# Control_part.net
KiCad netlist of a schematic drawn in Altium Designer
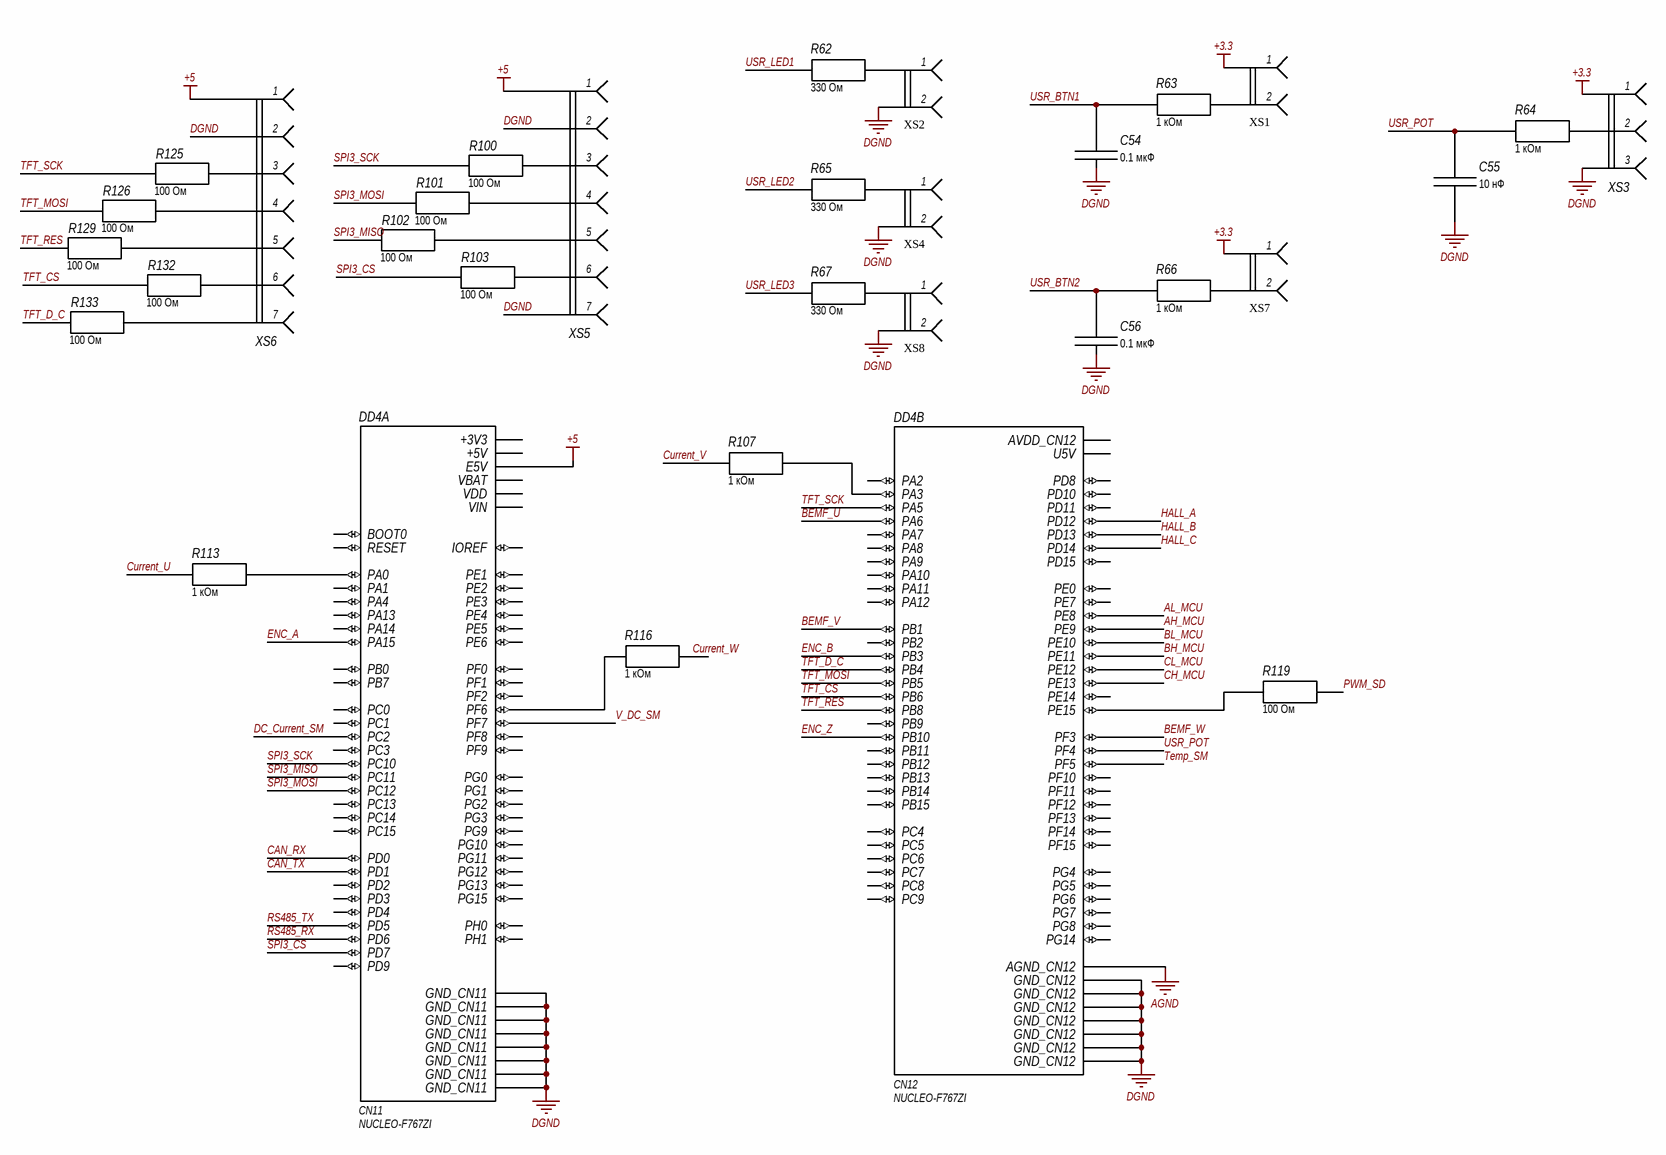
[diagram p0: Control_part.SchDoc]

(export (version "E")
  (design (tool "Eeschema 10.0.6"))
  (components
    (comp (ref "C54")
      (value "0.1 мкФ")
      (footprint "CC0603")
      (fields (field (name "VOLTAGE") "50 В") (field (name "Comment") "Capacitor"))
      (libsource (lib "Main_components") (part "Capacitor"))
    )
    (comp (ref "C55")
      (value "10 нФ")
      (footprint "CC0603")
      (fields (field (name "VOLTAGE") "50 В") (field (name "Comment") "Capacitor"))
      (libsource (lib "Main_components") (part "Capacitor"))
    )
    (comp (ref "C56")
      (value "0.1 мкФ")
      (footprint "CC0603")
      (fields (field (name "VOLTAGE") "50 В") (field (name "Comment") "Capacitor"))
      (libsource (lib "Main_components") (part "Capacitor"))
    )
    (comp (ref "DD4")
      (value "NUCLEO-F767ZI")
      (footprint "ST_NUCLEO-F767ZI")
      (fields (field (name "MF") "STMicroelectronics") (field (name "MP") "NUCLEO-F429ZI"))
      (libsource (lib "Microcircuits") (part "NUCLEO-F767ZI"))
    )
    (comp (ref "R62")
      (value "330 Ом")
      (footprint "RC1206")
      (fields (field (name "POWER") "250 мВт") (field (name "Comment") "Resistor"))
      (libsource (lib "Main_components") (part "Resistor"))
    )
    (comp (ref "R63")
      (value "1 кОм")
      (footprint "RC0603")
      (fields (field (name "POWER") "100 мВт") (field (name "Comment") "Resistor"))
      (libsource (lib "Main_components") (part "Resistor"))
    )
    (comp (ref "R64")
      (value "1 кОм")
      (footprint "RC0603")
      (fields (field (name "POWER") "100 мВт") (field (name "Comment") "Resistor"))
      (libsource (lib "Main_components") (part "Resistor"))
    )
    (comp (ref "R65")
      (value "330 Ом")
      (footprint "RC1206")
      (fields (field (name "POWER") "250 мВт") (field (name "Comment") "Resistor"))
      (libsource (lib "Main_components") (part "Resistor"))
    )
    (comp (ref "R66")
      (value "1 кОм")
      (footprint "RC0603")
      (fields (field (name "POWER") "100 мВт") (field (name "Comment") "Resistor"))
      (libsource (lib "Main_components") (part "Resistor"))
    )
    (comp (ref "R67")
      (value "330 Ом")
      (footprint "RC1206")
      (fields (field (name "POWER") "250 мВт") (field (name "Comment") "Resistor"))
      (libsource (lib "Main_components") (part "Resistor"))
    )
    (comp (ref "R100")
      (value "100 Ом")
      (footprint "RC0603")
      (fields (field (name "POWER") "100 мВт") (field (name "Comment") "Resistor"))
      (libsource (lib "Main_components") (part "Resistor"))
    )
    (comp (ref "R101")
      (value "100 Ом")
      (footprint "RC0603")
      (fields (field (name "POWER") "100 мВт") (field (name "Comment") "Resistor"))
      (libsource (lib "Main_components") (part "Resistor"))
    )
    (comp (ref "R102")
      (value "100 Ом")
      (footprint "RC0603")
      (fields (field (name "POWER") "100 мВт") (field (name "Comment") "Resistor"))
      (libsource (lib "Main_components") (part "Resistor"))
    )
    (comp (ref "R103")
      (value "100 Ом")
      (footprint "RC0603")
      (fields (field (name "POWER") "100 мВт") (field (name "Comment") "Resistor"))
      (libsource (lib "Main_components") (part "Resistor"))
    )
    (comp (ref "R107")
      (value "1 кОм")
      (footprint "RC0603")
      (fields (field (name "POWER") "100 мВт") (field (name "Comment") "Resistor"))
      (libsource (lib "Main_components") (part "Resistor"))
    )
    (comp (ref "R113")
      (value "1 кОм")
      (footprint "RC0603")
      (fields (field (name "POWER") "100 мВт") (field (name "Comment") "Resistor"))
      (libsource (lib "Main_components") (part "Resistor"))
    )
    (comp (ref "R116")
      (value "1 кОм")
      (footprint "RC0603")
      (fields (field (name "POWER") "100 мВт") (field (name "Comment") "Resistor"))
      (libsource (lib "Main_components") (part "Resistor"))
    )
    (comp (ref "R119")
      (value "100 Ом")
      (footprint "RC0603")
      (fields (field (name "POWER") "100 мВт") (field (name "Comment") "Resistor"))
      (libsource (lib "Main_components") (part "Resistor"))
    )
    (comp (ref "R125")
      (value "100 Ом")
      (footprint "RC0603")
      (fields (field (name "POWER") "100 мВт") (field (name "Comment") "Resistor"))
      (libsource (lib "Main_components") (part "Resistor"))
    )
    (comp (ref "R126")
      (value "100 Ом")
      (footprint "RC0603")
      (fields (field (name "POWER") "100 мВт") (field (name "Comment") "Resistor"))
      (libsource (lib "Main_components") (part "Resistor"))
    )
    (comp (ref "R129")
      (value "100 Ом")
      (footprint "RC0603")
      (fields (field (name "POWER") "100 мВт") (field (name "Comment") "Resistor"))
      (libsource (lib "Main_components") (part "Resistor"))
    )
    (comp (ref "R132")
      (value "100 Ом")
      (footprint "RC0603")
      (fields (field (name "POWER") "100 мВт") (field (name "Comment") "Resistor"))
      (libsource (lib "Main_components") (part "Resistor"))
    )
    (comp (ref "R133")
      (value "100 Ом")
      (footprint "RC0603")
      (fields (field (name "POWER") "100 мВт") (field (name "Comment") "Resistor"))
      (libsource (lib "Main_components") (part "Resistor"))
    )
    (comp (ref "XS1")
      (value "JST-Male-2")
      (footprint "JST-2")
      (libsource (lib "Connectors") (part "JST-Male-2"))
    )
    (comp (ref "XS2")
      (value "JST-Male-2")
      (footprint "JST-2")
      (libsource (lib "Connectors") (part "JST-Male-2"))
    )
    (comp (ref "XS3")
      (value "JST-Male-3")
      (footprint "JST-3")
      (libsource (lib "Connectors") (part "JST-Male-3"))
    )
    (comp (ref "XS4")
      (value "JST-Male-2")
      (footprint "JST-2")
      (libsource (lib "Connectors") (part "JST-Male-2"))
    )
    (comp (ref "XS5")
      (value "JST-Male-7")
      (footprint "JST-7")
      (libsource (lib "Connectors") (part "JST-Male-7"))
    )
    (comp (ref "XS6")
      (value "JST-Male-7")
      (footprint "JST-7")
      (libsource (lib "Connectors") (part "JST-Male-7"))
    )
    (comp (ref "XS7")
      (value "JST-Male-2")
      (footprint "JST-2")
      (libsource (lib "Connectors") (part "JST-Male-2"))
    )
    (comp (ref "XS8")
      (value "JST-Male-2")
      (footprint "JST-2")
      (libsource (lib "Connectors") (part "JST-Male-2"))
    )
  )
  (nets
    (net (code "1") (name "+3.3") (class "Default")
      (node (ref "XS1") (pin "1") (pinfunction "1_1") (pintype "passive"))
      (node (ref "XS3") (pin "1") (pinfunction "1_1") (pintype "passive"))
      (node (ref "XS7") (pin "1") (pinfunction "1_1") (pintype "passive"))
    )
    (net (code "2") (name "+5") (class "Default")
      (node (ref "DD4") (pin "CN11_6") (pinfunction "E5V_CN11_6") (pintype "power_in"))
      (node (ref "XS5") (pin "1") (pinfunction "1_1") (pintype "passive"))
      (node (ref "XS6") (pin "1") (pinfunction "1_1") (pintype "passive"))
    )
    (net (code "3") (name "/AH_MCU") (class "Default")
      (node (ref "DD4") (pin "CN12_52") (pinfunction "PE9_CN12_52") (pintype "bidirectional"))
    )
    (net (code "4") (name "/AL_MCU") (class "Default")
      (node (ref "DD4") (pin "CN12_40") (pinfunction "PE8_CN12_40") (pintype "bidirectional"))
    )
    (net (code "5") (name "/BEMF_U") (class "Default")
      (node (ref "DD4") (pin "CN12_13") (pinfunction "PA6_CN12_13") (pintype "bidirectional"))
    )
    (net (code "6") (name "/BEMF_V") (class "Default")
      (node (ref "DD4") (pin "CN12_24") (pinfunction "PB1_CN12_24") (pintype "bidirectional"))
    )
    (net (code "7") (name "/BEMF_W") (class "Default")
      (node (ref "DD4") (pin "CN12_58") (pinfunction "PF3_CN12_58") (pintype "bidirectional"))
    )
    (net (code "8") (name "/BH_MCU") (class "Default")
      (node (ref "DD4") (pin "CN12_56") (pinfunction "PE11_CN12_56") (pintype "bidirectional"))
    )
    (net (code "9") (name "/BL_MCU") (class "Default")
      (node (ref "DD4") (pin "CN12_47") (pinfunction "PE10_CN12_47") (pintype "bidirectional"))
    )
    (net (code "10") (name "/CAN_RX") (class "Default")
      (node (ref "DD4") (pin "CN11_57") (pinfunction "PD0_CN11_57") (pintype "bidirectional"))
    )
    (net (code "11") (name "/CAN_TX") (class "Default")
      (node (ref "DD4") (pin "CN11_55") (pinfunction "PD1_CN11_55") (pintype "bidirectional"))
    )
    (net (code "12") (name "/CH_MCU") (class "Default")
      (node (ref "DD4") (pin "CN12_55") (pinfunction "PE13_CN12_55") (pintype "bidirectional"))
    )
    (net (code "13") (name "/CL_MCU") (class "Default")
      (node (ref "DD4") (pin "CN12_49") (pinfunction "PE12_CN12_49") (pintype "bidirectional"))
    )
    (net (code "14") (name "/Current_U") (class "Default")
      (node (ref "R113") (pin "1") (pinfunction "1_1") (pintype "passive"))
    )
    (net (code "15") (name "/Current_V") (class "Default")
      (node (ref "R107") (pin "1") (pinfunction "1_1") (pintype "passive"))
    )
    (net (code "16") (name "/Current_W") (class "Default")
      (node (ref "R116") (pin "1") (pinfunction "1_1") (pintype "passive"))
    )
    (net (code "17") (name "/DC_Current_SM") (class "Default")
      (node (ref "DD4") (pin "CN11_35") (pinfunction "PC2_CN11_35") (pintype "bidirectional"))
    )
    (net (code "18") (name "/ENC_A") (class "Default")
      (node (ref "DD4") (pin "CN11_17") (pinfunction "PA15_CN11_17") (pintype "bidirectional"))
    )
    (net (code "19") (name "/ENC_B") (class "Default")
      (node (ref "DD4") (pin "CN12_31") (pinfunction "PB3_CN12_31") (pintype "bidirectional"))
    )
    (net (code "20") (name "/ENC_Z") (class "Default")
      (node (ref "DD4") (pin "CN12_25") (pinfunction "PB10_CN12_25") (pintype "bidirectional"))
    )
    (net (code "21") (name "/HALL_A") (class "Default")
      (node (ref "DD4") (pin "CN12_43") (pinfunction "PD12_CN12_43") (pintype "bidirectional"))
    )
    (net (code "22") (name "/HALL_B") (class "Default")
      (node (ref "DD4") (pin "CN12_41") (pinfunction "PD13_CN12_41") (pintype "bidirectional"))
    )
    (net (code "23") (name "/HALL_C") (class "Default")
      (node (ref "DD4") (pin "CN12_46") (pinfunction "PD14_CN12_46") (pintype "bidirectional"))
    )
    (net (code "24") (name "/PWM_SD") (class "Default")
      (node (ref "R119") (pin "1") (pinfunction "1_1") (pintype "passive"))
    )
    (net (code "25") (name "/RS485_RX") (class "Default")
      (node (ref "DD4") (pin "CN11_43") (pinfunction "PD6_CN11_43") (pintype "bidirectional"))
    )
    (net (code "26") (name "/RS485_TX") (class "Default")
      (node (ref "DD4") (pin "CN11_41") (pinfunction "PD5_CN11_41") (pintype "bidirectional"))
    )
    (net (code "27") (name "/SPI3_CS") (class "Default")
      (node (ref "DD4") (pin "CN11_45") (pinfunction "PD7_CN11_45") (pintype "bidirectional"))
      (node (ref "R103") (pin "2") (pinfunction "2_2") (pintype "passive"))
    )
    (net (code "28") (name "/SPI3_MISO") (class "Default")
      (node (ref "DD4") (pin "CN11_2") (pinfunction "PC11_CN11_2") (pintype "bidirectional"))
      (node (ref "R102") (pin "2") (pinfunction "2_2") (pintype "passive"))
    )
    (net (code "29") (name "/SPI3_MOSI") (class "Default")
      (node (ref "DD4") (pin "CN11_3") (pinfunction "PC12_CN11_3") (pintype "bidirectional"))
      (node (ref "R101") (pin "2") (pinfunction "2_2") (pintype "passive"))
    )
    (net (code "30") (name "/SPI3_SCK") (class "Default")
      (node (ref "DD4") (pin "CN11_1") (pinfunction "PC10_CN11_1") (pintype "bidirectional"))
      (node (ref "R100") (pin "2") (pinfunction "2_2") (pintype "passive"))
    )
    (net (code "31") (name "/TFT_CS") (class "Default")
      (node (ref "DD4") (pin "CN12_17") (pinfunction "PB6_CN12_17") (pintype "bidirectional"))
      (node (ref "R132") (pin "2") (pinfunction "2_2") (pintype "passive"))
    )
    (net (code "32") (name "/TFT_D_C") (class "Default")
      (node (ref "DD4") (pin "CN12_27") (pinfunction "PB4_CN12_27") (pintype "bidirectional"))
      (node (ref "R133") (pin "2") (pinfunction "2_2") (pintype "passive"))
    )
    (net (code "33") (name "/TFT_MOSI") (class "Default")
      (node (ref "DD4") (pin "CN12_29") (pinfunction "PB5_CN12_29") (pintype "bidirectional"))
      (node (ref "R126") (pin "2") (pinfunction "2_2") (pintype "passive"))
    )
    (net (code "34") (name "/TFT_RES") (class "Default")
      (node (ref "DD4") (pin "CN12_3") (pinfunction "PB8_CN12_3") (pintype "bidirectional"))
      (node (ref "R129") (pin "2") (pinfunction "2_2") (pintype "passive"))
    )
    (net (code "35") (name "/TFT_SCK") (class "Default")
      (node (ref "DD4") (pin "CN12_11") (pinfunction "PA5_CN12_11") (pintype "bidirectional"))
      (node (ref "R125") (pin "2") (pinfunction "2_2") (pintype "passive"))
    )
    (net (code "36") (name "/Temp_SM") (class "Default")
      (node (ref "DD4") (pin "CN12_36") (pinfunction "PF5_CN12_36") (pintype "bidirectional"))
    )
    (net (code "37") (name "/USR_BTN1") (class "Default")
      (node (ref "C54") (pin "2") (pinfunction "2_2") (pintype "passive"))
      (node (ref "R63") (pin "1") (pinfunction "1_1") (pintype "passive"))
    )
    (net (code "38") (name "/USR_BTN2") (class "Default")
      (node (ref "C56") (pin "2") (pinfunction "2_2") (pintype "passive"))
      (node (ref "R66") (pin "1") (pinfunction "1_1") (pintype "passive"))
    )
    (net (code "39") (name "/USR_LED1") (class "Default")
      (node (ref "R62") (pin "1") (pinfunction "1_1") (pintype "passive"))
    )
    (net (code "40") (name "/USR_LED2") (class "Default")
      (node (ref "R65") (pin "1") (pinfunction "1_1") (pintype "passive"))
    )
    (net (code "41") (name "/USR_LED3") (class "Default")
      (node (ref "R67") (pin "1") (pinfunction "1_1") (pintype "passive"))
    )
    (net (code "42") (name "/USR_POT") (class "Default")
      (node (ref "C55") (pin "2") (pinfunction "2_2") (pintype "passive"))
      (node (ref "DD4") (pin "CN12_38") (pinfunction "PF4_CN12_38") (pintype "bidirectional"))
      (node (ref "R64") (pin "1") (pinfunction "1_1") (pintype "passive"))
    )
    (net (code "43") (name "/V_DC_SM") (class "Default")
      (node (ref "DD4") (pin "CN11_11") (pinfunction "PF7_CN11_11") (pintype "bidirectional"))
    )
    (net (code "44") (name "AGND") (class "Default")
      (node (ref "DD4") (pin "CN12_32") (pinfunction "AGND_CN12_CN12_32") (pintype "power_in"))
    )
    (net (code "45") (name "DGND") (class "Default")
      (node (ref "C54") (pin "1") (pinfunction "1_1") (pintype "passive"))
      (node (ref "C55") (pin "1") (pinfunction "1_1") (pintype "passive"))
      (node (ref "C56") (pin "1") (pinfunction "1_1") (pintype "passive"))
      (node (ref "DD4") (pin "CN11_19") (pinfunction "GND_CN11_CN11_19") (pintype "power_in"))
      (node (ref "DD4") (pin "CN11_20") (pinfunction "GND_CN11_CN11_20") (pintype "power_in"))
      (node (ref "DD4") (pin "CN11_22") (pinfunction "GND_CN11_CN11_22") (pintype "power_in"))
      (node (ref "DD4") (pin "CN11_49") (pinfunction "GND_CN11_CN11_49") (pintype "power_in"))
      (node (ref "DD4") (pin "CN11_60") (pinfunction "GND_CN11_CN11_60") (pintype "power_in"))
      (node (ref "DD4") (pin "CN11_71") (pinfunction "GND_CN11_CN11_71") (pintype "power_in"))
      (node (ref "DD4") (pin "CN11_72") (pinfunction "GND_CN11_CN11_72") (pintype "power_in"))
      (node (ref "DD4") (pin "CN11_8") (pinfunction "GND_CN11_CN11_8") (pintype "power_in"))
      (node (ref "DD4") (pin "CN12_20") (pinfunction "GND_CN12_CN12_20") (pintype "power_in"))
      (node (ref "DD4") (pin "CN12_39") (pinfunction "GND_CN12_CN12_39") (pintype "power_in"))
      (node (ref "DD4") (pin "CN12_54") (pinfunction "GND_CN12_CN12_54") (pintype "power_in"))
      (node (ref "DD4") (pin "CN12_63") (pinfunction "GND_CN12_CN12_63") (pintype "power_in"))
      (node (ref "DD4") (pin "CN12_71") (pinfunction "GND_CN12_CN12_71") (pintype "power_in"))
      (node (ref "DD4") (pin "CN12_72") (pinfunction "GND_CN12_CN12_72") (pintype "power_in"))
      (node (ref "DD4") (pin "CN12_9") (pinfunction "GND_CN12_CN12_9") (pintype "power_in"))
      (node (ref "XS2") (pin "2") (pinfunction "2_2") (pintype "passive"))
      (node (ref "XS3") (pin "3") (pinfunction "3_3") (pintype "passive"))
      (node (ref "XS4") (pin "2") (pinfunction "2_2") (pintype "passive"))
      (node (ref "XS5") (pin "2") (pinfunction "2_2") (pintype "passive"))
      (node (ref "XS5") (pin "7") (pinfunction "7_7") (pintype "passive"))
      (node (ref "XS6") (pin "2") (pinfunction "2_2") (pintype "passive"))
      (node (ref "XS8") (pin "2") (pinfunction "2_2") (pintype "passive"))
    )
    (net (code "46") (name "Net-(DD4A-PA0)") (class "Default")
      (node (ref "DD4") (pin "CN11_28") (pinfunction "PA0_CN11_28") (pintype "bidirectional"))
      (node (ref "R113") (pin "2") (pinfunction "2_2") (pintype "passive"))
    )
    (net (code "47") (name "Net-(DD4A-PF6)") (class "Default")
      (node (ref "DD4") (pin "CN11_9") (pinfunction "PF6_CN11_9") (pintype "bidirectional"))
      (node (ref "R116") (pin "2") (pinfunction "2_2") (pintype "passive"))
    )
    (net (code "48") (name "Net-(DD4B-PA3)") (class "Default")
      (node (ref "DD4") (pin "CN12_37") (pinfunction "PA3_CN12_37") (pintype "bidirectional"))
      (node (ref "R107") (pin "2") (pinfunction "2_2") (pintype "passive"))
    )
    (net (code "49") (name "Net-(DD4B-PE15)") (class "Default")
      (node (ref "DD4") (pin "CN12_53") (pinfunction "PE15_CN12_53") (pintype "bidirectional"))
      (node (ref "R119") (pin "2") (pinfunction "2_2") (pintype "passive"))
    )
    (net (code "50") (name "Net-(R62-Pad2)") (class "Default")
      (node (ref "R62") (pin "2") (pinfunction "2_2") (pintype "passive"))
      (node (ref "XS2") (pin "1") (pinfunction "1_1") (pintype "passive"))
    )
    (net (code "51") (name "Net-(R63-Pad2)") (class "Default")
      (node (ref "R63") (pin "2") (pinfunction "2_2") (pintype "passive"))
      (node (ref "XS1") (pin "2") (pinfunction "2_2") (pintype "passive"))
    )
    (net (code "52") (name "Net-(R64-Pad2)") (class "Default")
      (node (ref "R64") (pin "2") (pinfunction "2_2") (pintype "passive"))
      (node (ref "XS3") (pin "2") (pinfunction "2_2") (pintype "passive"))
    )
    (net (code "53") (name "Net-(R65-Pad2)") (class "Default")
      (node (ref "R65") (pin "2") (pinfunction "2_2") (pintype "passive"))
      (node (ref "XS4") (pin "1") (pinfunction "1_1") (pintype "passive"))
    )
    (net (code "54") (name "Net-(R66-Pad2)") (class "Default")
      (node (ref "R66") (pin "2") (pinfunction "2_2") (pintype "passive"))
      (node (ref "XS7") (pin "2") (pinfunction "2_2") (pintype "passive"))
    )
    (net (code "55") (name "Net-(R67-Pad2)") (class "Default")
      (node (ref "R67") (pin "2") (pinfunction "2_2") (pintype "passive"))
      (node (ref "XS8") (pin "1") (pinfunction "1_1") (pintype "passive"))
    )
    (net (code "56") (name "Net-(R100-Pad1)") (class "Default")
      (node (ref "R100") (pin "1") (pinfunction "1_1") (pintype "passive"))
      (node (ref "XS5") (pin "3") (pinfunction "3_3") (pintype "passive"))
    )
    (net (code "57") (name "Net-(R101-Pad1)") (class "Default")
      (node (ref "R101") (pin "1") (pinfunction "1_1") (pintype "passive"))
      (node (ref "XS5") (pin "4") (pinfunction "4_4") (pintype "passive"))
    )
    (net (code "58") (name "Net-(R102-Pad1)") (class "Default")
      (node (ref "R102") (pin "1") (pinfunction "1_1") (pintype "passive"))
      (node (ref "XS5") (pin "5") (pinfunction "5_5") (pintype "passive"))
    )
    (net (code "59") (name "Net-(R103-Pad1)") (class "Default")
      (node (ref "R103") (pin "1") (pinfunction "1_1") (pintype "passive"))
      (node (ref "XS5") (pin "6") (pinfunction "6_6") (pintype "passive"))
    )
    (net (code "60") (name "Net-(R125-Pad1)") (class "Default")
      (node (ref "R125") (pin "1") (pinfunction "1_1") (pintype "passive"))
      (node (ref "XS6") (pin "3") (pinfunction "3_3") (pintype "passive"))
    )
    (net (code "61") (name "Net-(R126-Pad1)") (class "Default")
      (node (ref "R126") (pin "1") (pinfunction "1_1") (pintype "passive"))
      (node (ref "XS6") (pin "4") (pinfunction "4_4") (pintype "passive"))
    )
    (net (code "62") (name "Net-(R129-Pad1)") (class "Default")
      (node (ref "R129") (pin "1") (pinfunction "1_1") (pintype "passive"))
      (node (ref "XS6") (pin "5") (pinfunction "5_5") (pintype "passive"))
    )
    (net (code "63") (name "Net-(R132-Pad1)") (class "Default")
      (node (ref "R132") (pin "1") (pinfunction "1_1") (pintype "passive"))
      (node (ref "XS6") (pin "6") (pinfunction "6_6") (pintype "passive"))
    )
    (net (code "64") (name "Net-(R133-Pad1)") (class "Default")
      (node (ref "R133") (pin "1") (pinfunction "1_1") (pintype "passive"))
      (node (ref "XS6") (pin "7") (pinfunction "7_7") (pintype "passive"))
    )
    (net (code "65") (name "unconnected-(DD4A-+3V3-PadCN11_16)") (class "Default")
      (node (ref "DD4") (pin "CN11_16") (pinfunction "+3V3_CN11_16") (pintype "power_in"))
    )
    (net (code "66") (name "unconnected-(DD4A-+5V-PadCN11_18)") (class "Default")
      (node (ref "DD4") (pin "CN11_18") (pinfunction "+5V_CN11_18") (pintype "power_in"))
    )
    (net (code "67") (name "unconnected-(DD4A-BOOT0-PadCN11_7)") (class "Default")
      (node (ref "DD4") (pin "CN11_7") (pinfunction "BOOT0_CN11_7") (pintype "bidirectional"))
    )
    (net (code "68") (name "unconnected-(DD4A-IOREF-PadCN11_12)") (class "Default")
      (node (ref "DD4") (pin "CN11_12") (pinfunction "IOREF_CN11_12") (pintype "bidirectional"))
    )
    (net (code "69") (name "unconnected-(DD4A-PA1-PadCN11_30)") (class "Default")
      (node (ref "DD4") (pin "CN11_30") (pinfunction "PA1_CN11_30") (pintype "bidirectional"))
    )
    (net (code "70") (name "unconnected-(DD4A-PA4-PadCN11_32)") (class "Default")
      (node (ref "DD4") (pin "CN11_32") (pinfunction "PA4_CN11_32") (pintype "bidirectional"))
    )
    (net (code "71") (name "unconnected-(DD4A-PA13-PadCN11_13)") (class "Default")
      (node (ref "DD4") (pin "CN11_13") (pinfunction "PA13_CN11_13") (pintype "bidirectional"))
    )
    (net (code "72") (name "unconnected-(DD4A-PA14-PadCN11_15)") (class "Default")
      (node (ref "DD4") (pin "CN11_15") (pinfunction "PA14_CN11_15") (pintype "bidirectional"))
    )
    (net (code "73") (name "unconnected-(DD4A-PB0-PadCN11_34)") (class "Default")
      (node (ref "DD4") (pin "CN11_34") (pinfunction "PB0_CN11_34") (pintype "bidirectional"))
    )
    (net (code "74") (name "unconnected-(DD4A-PB7-PadCN11_21)") (class "Default")
      (node (ref "DD4") (pin "CN11_21") (pinfunction "PB7_CN11_21") (pintype "bidirectional"))
    )
    (net (code "75") (name "unconnected-(DD4A-PC0-PadCN11_38)") (class "Default")
      (node (ref "DD4") (pin "CN11_38") (pinfunction "PC0_CN11_38") (pintype "bidirectional"))
    )
    (net (code "76") (name "unconnected-(DD4A-PC1-PadCN11_36)") (class "Default")
      (node (ref "DD4") (pin "CN11_36") (pinfunction "PC1_CN11_36") (pintype "bidirectional"))
    )
    (net (code "77") (name "unconnected-(DD4A-PC3-PadCN11_37)") (class "Default")
      (node (ref "DD4") (pin "CN11_37") (pinfunction "PC3_CN11_37") (pintype "bidirectional"))
    )
    (net (code "78") (name "unconnected-(DD4A-PC13-PadCN11_23)") (class "Default")
      (node (ref "DD4") (pin "CN11_23") (pinfunction "PC13_CN11_23") (pintype "bidirectional"))
    )
    (net (code "79") (name "unconnected-(DD4A-PC14-PadCN11_25)") (class "Default")
      (node (ref "DD4") (pin "CN11_25") (pinfunction "PC14_CN11_25") (pintype "bidirectional"))
    )
    (net (code "80") (name "unconnected-(DD4A-PC15-PadCN11_27)") (class "Default")
      (node (ref "DD4") (pin "CN11_27") (pinfunction "PC15_CN11_27") (pintype "bidirectional"))
    )
    (net (code "81") (name "unconnected-(DD4A-PD2-PadCN11_4)") (class "Default")
      (node (ref "DD4") (pin "CN11_4") (pinfunction "PD2_CN11_4") (pintype "bidirectional"))
    )
    (net (code "82") (name "unconnected-(DD4A-PD3-PadCN11_40)") (class "Default")
      (node (ref "DD4") (pin "CN11_40") (pinfunction "PD3_CN11_40") (pintype "bidirectional"))
    )
    (net (code "83") (name "unconnected-(DD4A-PD4-PadCN11_39)") (class "Default")
      (node (ref "DD4") (pin "CN11_39") (pinfunction "PD4_CN11_39") (pintype "bidirectional"))
    )
    (net (code "84") (name "unconnected-(DD4A-PD9-PadCN11_69)") (class "Default")
      (node (ref "DD4") (pin "CN11_69") (pinfunction "PD9_CN11_69") (pintype "bidirectional"))
    )
    (net (code "85") (name "unconnected-(DD4A-PE1-PadCN11_61)") (class "Default")
      (node (ref "DD4") (pin "CN11_61") (pinfunction "PE1_CN11_61") (pintype "bidirectional"))
    )
    (net (code "86") (name "unconnected-(DD4A-PE2-PadCN11_46)") (class "Default")
      (node (ref "DD4") (pin "CN11_46") (pinfunction "PE2_CN11_46") (pintype "bidirectional"))
    )
    (net (code "87") (name "unconnected-(DD4A-PE3-PadCN11_47)") (class "Default")
      (node (ref "DD4") (pin "CN11_47") (pinfunction "PE3_CN11_47") (pintype "bidirectional"))
    )
    (net (code "88") (name "unconnected-(DD4A-PE4-PadCN11_48)") (class "Default")
      (node (ref "DD4") (pin "CN11_48") (pinfunction "PE4_CN11_48") (pintype "bidirectional"))
    )
    (net (code "89") (name "unconnected-(DD4A-PE5-PadCN11_50)") (class "Default")
      (node (ref "DD4") (pin "CN11_50") (pinfunction "PE5_CN11_50") (pintype "bidirectional"))
    )
    (net (code "90") (name "unconnected-(DD4A-PE6-PadCN11_62)") (class "Default")
      (node (ref "DD4") (pin "CN11_62") (pinfunction "PE6_CN11_62") (pintype "bidirectional"))
    )
    (net (code "91") (name "unconnected-(DD4A-PF0-PadCN11_53)") (class "Default")
      (node (ref "DD4") (pin "CN11_53") (pinfunction "PF0_CN11_53") (pintype "bidirectional"))
    )
    (net (code "92") (name "unconnected-(DD4A-PF1-PadCN11_51)") (class "Default")
      (node (ref "DD4") (pin "CN11_51") (pinfunction "PF1_CN11_51") (pintype "bidirectional"))
    )
    (net (code "93") (name "unconnected-(DD4A-PF2-PadCN11_52)") (class "Default")
      (node (ref "DD4") (pin "CN11_52") (pinfunction "PF2_CN11_52") (pintype "bidirectional"))
    )
    (net (code "94") (name "unconnected-(DD4A-PF8-PadCN11_54)") (class "Default")
      (node (ref "DD4") (pin "CN11_54") (pinfunction "PF8_CN11_54") (pintype "bidirectional"))
    )
    (net (code "95") (name "unconnected-(DD4A-PF9-PadCN11_56)") (class "Default")
      (node (ref "DD4") (pin "CN11_56") (pinfunction "PF9_CN11_56") (pintype "bidirectional"))
    )
    (net (code "96") (name "unconnected-(DD4A-PG0-PadCN11_59)") (class "Default")
      (node (ref "DD4") (pin "CN11_59") (pinfunction "PG0_CN11_59") (pintype "bidirectional"))
    )
    (net (code "97") (name "unconnected-(DD4A-PG1-PadCN11_58)") (class "Default")
      (node (ref "DD4") (pin "CN11_58") (pinfunction "PG1_CN11_58") (pintype "bidirectional"))
    )
    (net (code "98") (name "unconnected-(DD4A-PG2-PadCN11_42)") (class "Default")
      (node (ref "DD4") (pin "CN11_42") (pinfunction "PG2_CN11_42") (pintype "bidirectional"))
    )
    (net (code "99") (name "unconnected-(DD4A-PG3-PadCN11_44)") (class "Default")
      (node (ref "DD4") (pin "CN11_44") (pinfunction "PG3_CN11_44") (pintype "bidirectional"))
    )
    (net (code "100") (name "unconnected-(DD4A-PG9-PadCN11_63)") (class "Default")
      (node (ref "DD4") (pin "CN11_63") (pinfunction "PG9_CN11_63") (pintype "bidirectional"))
    )
    (net (code "101") (name "unconnected-(DD4A-PG10-PadCN11_66)") (class "Default")
      (node (ref "DD4") (pin "CN11_66") (pinfunction "PG10_CN11_66") (pintype "bidirectional"))
    )
    (net (code "102") (name "unconnected-(DD4A-PG11-PadCN11_70)") (class "Default")
      (node (ref "DD4") (pin "CN11_70") (pinfunction "PG11_CN11_70") (pintype "bidirectional"))
    )
    (net (code "103") (name "unconnected-(DD4A-PG12-PadCN11_65)") (class "Default")
      (node (ref "DD4") (pin "CN11_65") (pinfunction "PG12_CN11_65") (pintype "bidirectional"))
    )
    (net (code "104") (name "unconnected-(DD4A-PG13-PadCN11_68)") (class "Default")
      (node (ref "DD4") (pin "CN11_68") (pinfunction "PG13_CN11_68") (pintype "bidirectional"))
    )
    (net (code "105") (name "unconnected-(DD4A-PG15-PadCN11_64)") (class "Default")
      (node (ref "DD4") (pin "CN11_64") (pinfunction "PG15_CN11_64") (pintype "bidirectional"))
    )
    (net (code "106") (name "unconnected-(DD4A-PH0-PadCN11_29)") (class "Default")
      (node (ref "DD4") (pin "CN11_29") (pinfunction "PH0_CN11_29") (pintype "bidirectional"))
    )
    (net (code "107") (name "unconnected-(DD4A-PH1-PadCN11_31)") (class "Default")
      (node (ref "DD4") (pin "CN11_31") (pinfunction "PH1_CN11_31") (pintype "bidirectional"))
    )
    (net (code "108") (name "unconnected-(DD4A-RESET-PadCN11_14)") (class "Default")
      (node (ref "DD4") (pin "CN11_14") (pinfunction "RESET_CN11_14") (pintype "bidirectional"))
    )
    (net (code "109") (name "unconnected-(DD4A-VBAT-PadCN11_33)") (class "Default")
      (node (ref "DD4") (pin "CN11_33") (pinfunction "VBAT_CN11_33") (pintype "power_in"))
    )
    (net (code "110") (name "unconnected-(DD4A-VDD-PadCN11_5)") (class "Default")
      (node (ref "DD4") (pin "CN11_5") (pinfunction "VDD_CN11_5") (pintype "power_in"))
    )
    (net (code "111") (name "unconnected-(DD4A-VIN-PadCN11_24)") (class "Default")
      (node (ref "DD4") (pin "CN11_24") (pinfunction "VIN_CN11_24") (pintype "power_in"))
    )
    (net (code "112") (name "unconnected-(DD4B-AVDD_CN12-PadCN12_7)") (class "Default")
      (node (ref "DD4") (pin "CN12_7") (pinfunction "AVDD_CN12_CN12_7") (pintype "power_in"))
    )
    (net (code "113") (name "unconnected-(DD4B-PA2-PadCN12_35)") (class "Default")
      (node (ref "DD4") (pin "CN12_35") (pinfunction "PA2_CN12_35") (pintype "bidirectional"))
    )
    (net (code "114") (name "unconnected-(DD4B-PA7-PadCN12_15)") (class "Default")
      (node (ref "DD4") (pin "CN12_15") (pinfunction "PA7_CN12_15") (pintype "bidirectional"))
    )
    (net (code "115") (name "unconnected-(DD4B-PA8-PadCN12_23)") (class "Default")
      (node (ref "DD4") (pin "CN12_23") (pinfunction "PA8_CN12_23") (pintype "bidirectional"))
    )
    (net (code "116") (name "unconnected-(DD4B-PA9-PadCN12_21)") (class "Default")
      (node (ref "DD4") (pin "CN12_21") (pinfunction "PA9_CN12_21") (pintype "bidirectional"))
    )
    (net (code "117") (name "unconnected-(DD4B-PA10-PadCN12_33)") (class "Default")
      (node (ref "DD4") (pin "CN12_33") (pinfunction "PA10_CN12_33") (pintype "bidirectional"))
    )
    (net (code "118") (name "unconnected-(DD4B-PA11-PadCN12_14)") (class "Default")
      (node (ref "DD4") (pin "CN12_14") (pinfunction "PA11_CN12_14") (pintype "bidirectional"))
    )
    (net (code "119") (name "unconnected-(DD4B-PA12-PadCN12_12)") (class "Default")
      (node (ref "DD4") (pin "CN12_12") (pinfunction "PA12_CN12_12") (pintype "bidirectional"))
    )
    (net (code "120") (name "unconnected-(DD4B-PB2-PadCN12_22)") (class "Default")
      (node (ref "DD4") (pin "CN12_22") (pinfunction "PB2_CN12_22") (pintype "bidirectional"))
    )
    (net (code "121") (name "unconnected-(DD4B-PB9-PadCN12_5)") (class "Default")
      (node (ref "DD4") (pin "CN12_5") (pinfunction "PB9_CN12_5") (pintype "bidirectional"))
    )
    (net (code "122") (name "unconnected-(DD4B-PB11-PadCN12_18)") (class "Default")
      (node (ref "DD4") (pin "CN12_18") (pinfunction "PB11_CN12_18") (pintype "bidirectional"))
    )
    (net (code "123") (name "unconnected-(DD4B-PB12-PadCN12_16)") (class "Default")
      (node (ref "DD4") (pin "CN12_16") (pinfunction "PB12_CN12_16") (pintype "bidirectional"))
    )
    (net (code "124") (name "unconnected-(DD4B-PB13-PadCN12_30)") (class "Default")
      (node (ref "DD4") (pin "CN12_30") (pinfunction "PB13_CN12_30") (pintype "bidirectional"))
    )
    (net (code "125") (name "unconnected-(DD4B-PB14-PadCN12_28)") (class "Default")
      (node (ref "DD4") (pin "CN12_28") (pinfunction "PB14_CN12_28") (pintype "bidirectional"))
    )
    (net (code "126") (name "unconnected-(DD4B-PB15-PadCN12_26)") (class "Default")
      (node (ref "DD4") (pin "CN12_26") (pinfunction "PB15_CN12_26") (pintype "bidirectional"))
    )
    (net (code "127") (name "unconnected-(DD4B-PC4-PadCN12_34)") (class "Default")
      (node (ref "DD4") (pin "CN12_34") (pinfunction "PC4_CN12_34") (pintype "bidirectional"))
    )
    (net (code "128") (name "unconnected-(DD4B-PC5-PadCN12_6)") (class "Default")
      (node (ref "DD4") (pin "CN12_6") (pinfunction "PC5_CN12_6") (pintype "bidirectional"))
    )
    (net (code "129") (name "unconnected-(DD4B-PC6-PadCN12_4)") (class "Default")
      (node (ref "DD4") (pin "CN12_4") (pinfunction "PC6_CN12_4") (pintype "bidirectional"))
    )
    (net (code "130") (name "unconnected-(DD4B-PC7-PadCN12_19)") (class "Default")
      (node (ref "DD4") (pin "CN12_19") (pinfunction "PC7_CN12_19") (pintype "bidirectional"))
    )
    (net (code "131") (name "unconnected-(DD4B-PC8-PadCN12_2)") (class "Default")
      (node (ref "DD4") (pin "CN12_2") (pinfunction "PC8_CN12_2") (pintype "bidirectional"))
    )
    (net (code "132") (name "unconnected-(DD4B-PC9-PadCN12_1)") (class "Default")
      (node (ref "DD4") (pin "CN12_1") (pinfunction "PC9_CN12_1") (pintype "bidirectional"))
    )
    (net (code "133") (name "unconnected-(DD4B-PD8-PadCN12_10)") (class "Default")
      (node (ref "DD4") (pin "CN12_10") (pinfunction "PD8_CN12_10") (pintype "bidirectional"))
    )
    (net (code "134") (name "unconnected-(DD4B-PD10-PadCN12_65)") (class "Default")
      (node (ref "DD4") (pin "CN12_65") (pinfunction "PD10_CN12_65") (pintype "bidirectional"))
    )
    (net (code "135") (name "unconnected-(DD4B-PD11-PadCN12_45)") (class "Default")
      (node (ref "DD4") (pin "CN12_45") (pinfunction "PD11_CN12_45") (pintype "bidirectional"))
    )
    (net (code "136") (name "unconnected-(DD4B-PD15-PadCN12_48)") (class "Default")
      (node (ref "DD4") (pin "CN12_48") (pinfunction "PD15_CN12_48") (pintype "bidirectional"))
    )
    (net (code "137") (name "unconnected-(DD4B-PE0-PadCN12_64)") (class "Default")
      (node (ref "DD4") (pin "CN12_64") (pinfunction "PE0_CN12_64") (pintype "bidirectional"))
    )
    (net (code "138") (name "unconnected-(DD4B-PE7-PadCN12_44)") (class "Default")
      (node (ref "DD4") (pin "CN12_44") (pinfunction "PE7_CN12_44") (pintype "bidirectional"))
    )
    (net (code "139") (name "unconnected-(DD4B-PE14-PadCN12_51)") (class "Default")
      (node (ref "DD4") (pin "CN12_51") (pinfunction "PE14_CN12_51") (pintype "bidirectional"))
    )
    (net (code "140") (name "unconnected-(DD4B-PF10-PadCN12_42)") (class "Default")
      (node (ref "DD4") (pin "CN12_42") (pinfunction "PF10_CN12_42") (pintype "bidirectional"))
    )
    (net (code "141") (name "unconnected-(DD4B-PF11-PadCN12_62)") (class "Default")
      (node (ref "DD4") (pin "CN12_62") (pinfunction "PF11_CN12_62") (pintype "bidirectional"))
    )
    (net (code "142") (name "unconnected-(DD4B-PF12-PadCN12_59)") (class "Default")
      (node (ref "DD4") (pin "CN12_59") (pinfunction "PF12_CN12_59") (pintype "bidirectional"))
    )
    (net (code "143") (name "unconnected-(DD4B-PF13-PadCN12_57)") (class "Default")
      (node (ref "DD4") (pin "CN12_57") (pinfunction "PF13_CN12_57") (pintype "bidirectional"))
    )
    (net (code "144") (name "unconnected-(DD4B-PF14-PadCN12_50)") (class "Default")
      (node (ref "DD4") (pin "CN12_50") (pinfunction "PF14_CN12_50") (pintype "bidirectional"))
    )
    (net (code "145") (name "unconnected-(DD4B-PF15-PadCN12_60)") (class "Default")
      (node (ref "DD4") (pin "CN12_60") (pinfunction "PF15_CN12_60") (pintype "bidirectional"))
    )
    (net (code "146") (name "unconnected-(DD4B-PG4-PadCN12_69)") (class "Default")
      (node (ref "DD4") (pin "CN12_69") (pinfunction "PG4_CN12_69") (pintype "bidirectional"))
    )
    (net (code "147") (name "unconnected-(DD4B-PG5-PadCN12_68)") (class "Default")
      (node (ref "DD4") (pin "CN12_68") (pinfunction "PG5_CN12_68") (pintype "bidirectional"))
    )
    (net (code "148") (name "unconnected-(DD4B-PG6-PadCN12_70)") (class "Default")
      (node (ref "DD4") (pin "CN12_70") (pinfunction "PG6_CN12_70") (pintype "bidirectional"))
    )
    (net (code "149") (name "unconnected-(DD4B-PG7-PadCN12_67)") (class "Default")
      (node (ref "DD4") (pin "CN12_67") (pinfunction "PG7_CN12_67") (pintype "bidirectional"))
    )
    (net (code "150") (name "unconnected-(DD4B-PG8-PadCN12_66)") (class "Default")
      (node (ref "DD4") (pin "CN12_66") (pinfunction "PG8_CN12_66") (pintype "bidirectional"))
    )
    (net (code "151") (name "unconnected-(DD4B-PG14-PadCN12_61)") (class "Default")
      (node (ref "DD4") (pin "CN12_61") (pinfunction "PG14_CN12_61") (pintype "bidirectional"))
    )
    (net (code "152") (name "unconnected-(DD4B-U5V-PadCN12_8)") (class "Default")
      (node (ref "DD4") (pin "CN12_8") (pinfunction "U5V_CN12_8") (pintype "power_in"))
    )
  )
)
